# automatic_streetlight_with_LDR.net
KiCad netlist of a schematic drawn in EAGLE
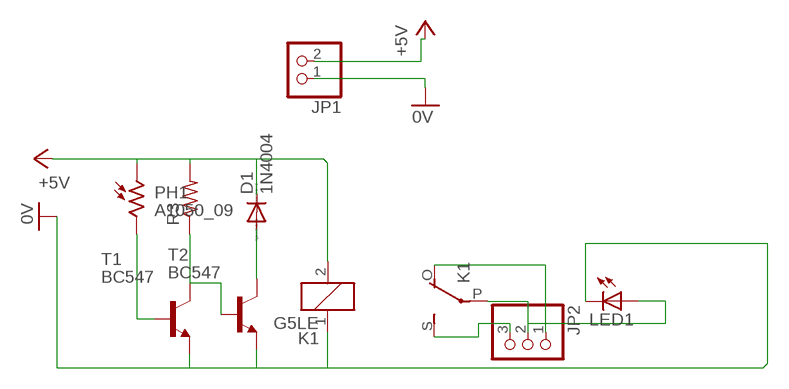
[diagram p0: schematic, sheet 1]

(export (version "E")
  (design (tool "Eeschema 10.0.6"))
  (components
    (comp (ref "D1")
      (value "1N4004")
      (footprint "eagle-import:DO41-10")
      (libsource (lib "eagle-import") (part "1N4004"))
    )
    (comp (ref "JP1")
      (value "PINHD-1X2")
      (footprint "eagle-import:1X02")
      (libsource (lib "eagle-import") (part "PINHD-1X2"))
    )
    (comp (ref "JP2")
      (value "PINHD-1X3")
      (footprint "eagle-import:1X03")
      (libsource (lib "eagle-import") (part "PINHD-1X3"))
    )
    (comp (ref "K1")
      (value "G5LE")
      (footprint "eagle-import:G5LE")
      (libsource (lib "eagle-import") (part "G5LE"))
    )
    (comp (ref "LED1")
      (value "LED3MM")
      (footprint "eagle-import:LED3MM")
      (libsource (lib "eagle-import") (part "LED3MM"))
    )
    (comp (ref "PH1")
      (value "A1050_09")
      (footprint "eagle-import:T0-46-A10XX")
      (libsource (lib "eagle-import") (part "A1050_09"))
    )
    (comp (ref "R3")
      (value "R-US_0207/10")
      (footprint "eagle-import:0207_10")
      (libsource (lib "eagle-import") (part "R-US_0207/10"))
    )
    (comp (ref "T1")
      (value "BC547")
      (footprint "eagle-import:TO92")
      (libsource (lib "eagle-import") (part "BC547"))
    )
    (comp (ref "T2")
      (value "BC547")
      (footprint "eagle-import:TO92")
      (libsource (lib "eagle-import") (part "BC547"))
    )
  )
  (nets
    (net (code "1") (name "+5V") (class "Default")
      (node (ref "D1") (pin "C") (pinfunction "C_C") (pintype "passive"))
      (node (ref "JP1") (pin "2") (pinfunction "2_2") (pintype "passive"))
      (node (ref "K1") (pin "2") (pinfunction "2_2") (pintype "passive"))
      (node (ref "PH1") (pin "1") (pinfunction "1_1") (pintype "passive"))
      (node (ref "R3") (pin "2") (pinfunction "2_2") (pintype "passive"))
    )
    (net (code "2") (name "0V") (class "Default")
      (node (ref "JP1") (pin "1") (pinfunction "1_1") (pintype "passive"))
      (node (ref "K1") (pin "1") (pinfunction "1_1") (pintype "passive"))
      (node (ref "LED1") (pin "K") (pinfunction "C_K") (pintype "passive"))
      (node (ref "T1") (pin "1") (pinfunction "E_1") (pintype "passive"))
      (node (ref "T2") (pin "1") (pinfunction "E_1") (pintype "passive"))
    )
    (net (code "3") (name "Net-(JP2-Pad1)") (class "Default")
      (node (ref "JP2") (pin "1") (pinfunction "1_1") (pintype "passive"))
      (node (ref "K1") (pin "O") (pinfunction "O_O") (pintype "passive"))
    )
    (net (code "4") (name "Net-(JP2-Pad2)") (class "Default")
      (node (ref "JP2") (pin "2") (pinfunction "2_2") (pintype "passive"))
      (node (ref "K1") (pin "P") (pinfunction "P_P") (pintype "passive"))
      (node (ref "LED1") (pin "A") (pinfunction "A_A") (pintype "passive"))
    )
    (net (code "5") (name "Net-(JP2-Pad3)") (class "Default")
      (node (ref "JP2") (pin "3") (pinfunction "3_3") (pintype "passive"))
      (node (ref "K1") (pin "S") (pinfunction "S_S") (pintype "passive"))
    )
    (net (code "6") (name "Net-(T1-B)") (class "Default")
      (node (ref "PH1") (pin "2") (pinfunction "2_2") (pintype "passive"))
      (node (ref "T1") (pin "2") (pinfunction "B_2") (pintype "passive"))
    )
    (net (code "7") (name "Net-(T1-C)") (class "Default")
      (node (ref "R3") (pin "1") (pinfunction "1_1") (pintype "passive"))
      (node (ref "T1") (pin "3") (pinfunction "C_3") (pintype "passive"))
      (node (ref "T2") (pin "2") (pinfunction "B_2") (pintype "passive"))
    )
    (net (code "8") (name "Net-(T2-C)") (class "Default")
      (node (ref "D1") (pin "A") (pinfunction "A_A") (pintype "passive"))
      (node (ref "T2") (pin "3") (pinfunction "C_3") (pintype "passive"))
    )
  )
)
